# Lab_8_v3.net
KiCad netlist of a schematic drawn in Altium Designer
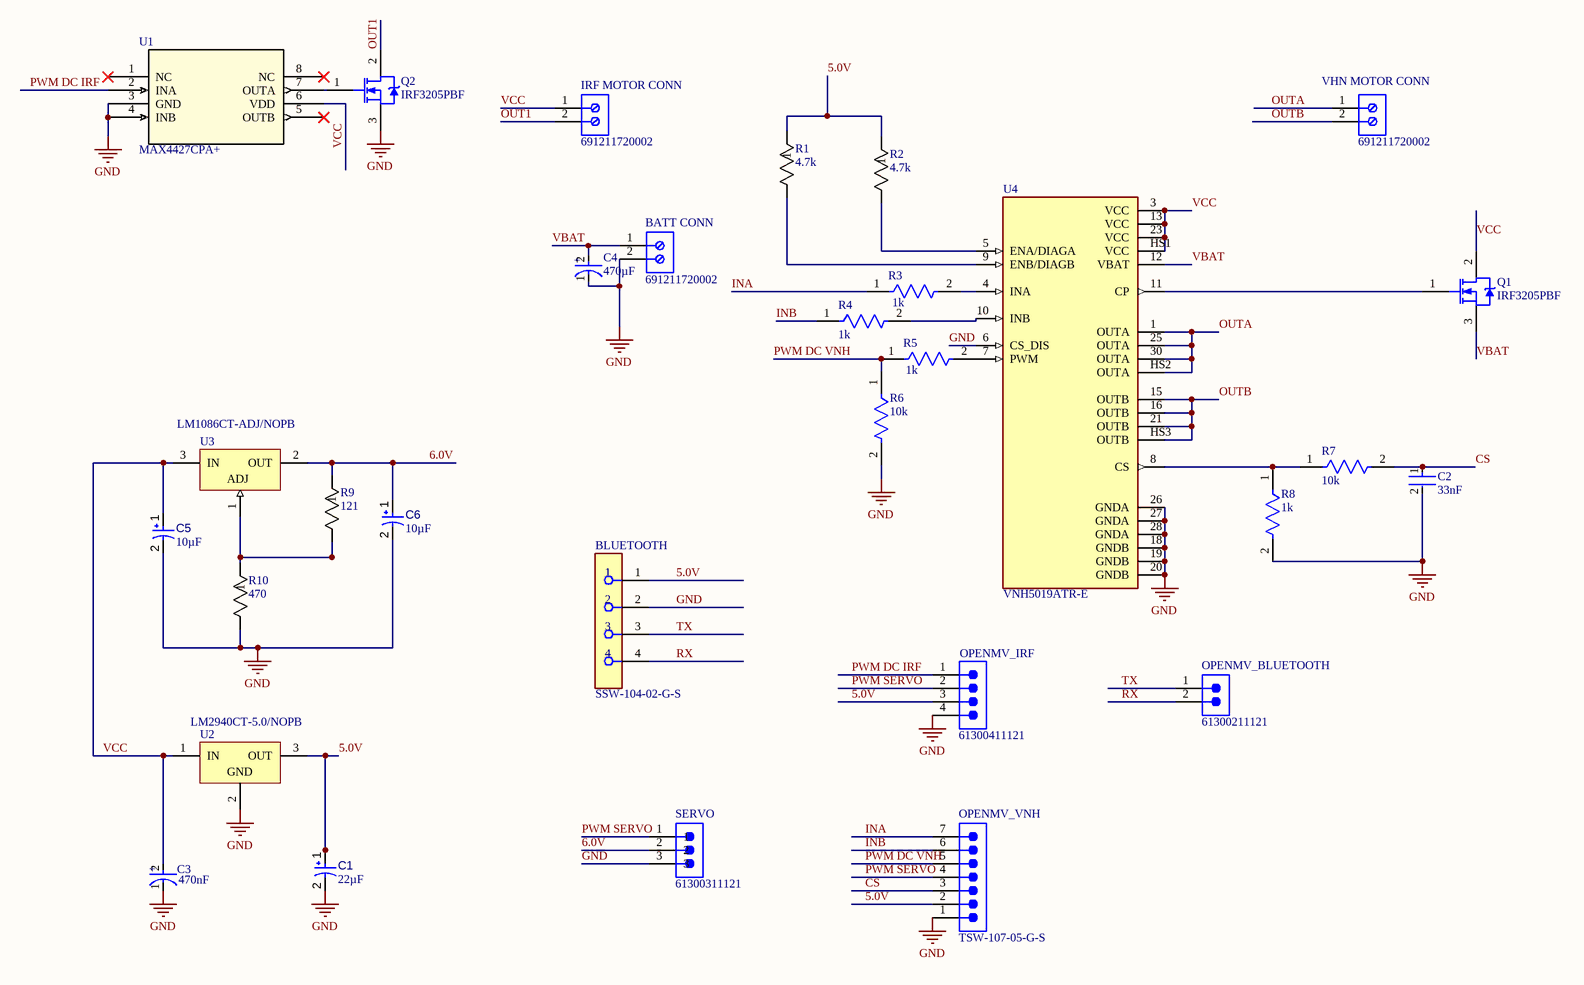
[diagram p0: Lab_8_v3.SchDoc]

(export (version "E")
  (design (tool "Eeschema 10.0.6"))
  (components
    (comp (ref "BATT CONN")
      (value "691211720002")
      (footprint "691211720002")
      (fields (field (name "VOLTAGE") "300V"))
      (libsource (lib "Altium Content Vault") (part "TBL - 1R - 02P - Screw"))
    )
    (comp (ref "BLUETOOTH")
      (value "SSW-104-02-G-S")
      (footprint "FP-SSW-104-02-G-S-MFG")
      (libsource (lib "Haaris Tahir-Kheli") (part "56792406a6bd5c25e158f553ecd1aa7"))
    )
    (comp (ref "C1")
      (value "22µF")
      (footprint "CAPPR55-200-1100X500X1200")
      (description "Aluminum Electrolytic Capacitor, 22 uF, +/- 20%, 50 V, -40 to 85 degC, 2-Pin THD, RoHS, Bulk")
      (fields (field (name "MANUFACTURER") "Panasonic") (field (name "TOLERANCE") "20%"))
      (libsource (lib "University of California, Davis") (part "CAP-P-2"))
    )
    (comp (ref "C2")
      (value "33nF")
      (footprint "FP-565R30GASS33-MFG")
      (description "565R30GASS33 33nF 3 kV dc Ceramic Single Layer Capacitor; Z5U Dielectric Radial 565R Series")
      (fields (field (name "VOLTAGE") "3kV") (field (name "TOLERANCE") "20%"))
      (libsource (lib "Altium Content Vault") (part "02cd4be3c70576c341d710602a673aa"))
    )
    (comp (ref "C3")
      (value "470nF")
      (footprint "FP-RAD-TH-D_5_0_5-L_11_1-MFG")
      (fields (field (name "Comment") "EEU-EB1JR47S"))
      (libsource (lib "Haaris Tahir-Kheli") (part "a00bbbee19879c290e62620ae7e47b1"))
    )
    (comp (ref "C4")
      (value "470µF")
      (footprint "FP-MAL202136471E3-MFG")
      (fields (field (name "Comment") "MAL202136471E3"))
      (libsource (lib "Haaris Tahir-Kheli") (part "a00bbbee19879c290e62620ae7e47b1"))
    )
    (comp (ref "C5")
      (value "10µF")
      (footprint "CAPPR55-200-1100X500X1200")
      (description "Aluminum Electrolytic Capacitor, 10 uF, +/- 20%, 50 V, -40 to 85 degC, 2-Pin THD, RoHS, Bulk")
      (fields (field (name "MANUFACTURER") "Panasonic") (field (name "TOLERANCE") "20%"))
      (libsource (lib "University of California, Davis") (part "CAP-P-2"))
    )
    (comp (ref "C6")
      (value "10µF")
      (footprint "CAPPR55-200-1100X500X1200")
      (description "Aluminum Electrolytic Capacitor, 10 uF, +/- 20%, 50 V, -40 to 85 degC, 2-Pin THD, RoHS, Bulk")
      (fields (field (name "MANUFACTURER") "Panasonic") (field (name "TOLERANCE") "20%"))
      (libsource (lib "University of California, Davis") (part "CAP-P-2"))
    )
    (comp (ref "IRF MOTOR CONN")
      (value "691211720002")
      (footprint "691211720002")
      (fields (field (name "VOLTAGE") "300V"))
      (libsource (lib "Altium Content Vault") (part "TBL - 1R - 02P - Screw"))
    )
    (comp (ref "OPENMV_BLUETOOTH")
      (value "61300211121")
      (footprint "61300211121")
      (libsource (lib "Haaris Tahir-Kheli") (part "Header_Male_1R_02P"))
    )
    (comp (ref "OPENMV_IRF")
      (value "61300411121")
      (footprint "61300411121")
      (libsource (lib "Haaris Tahir-Kheli") (part "Header_Male_1R_04P"))
    )
    (comp (ref "OPENMV_VNH")
      (value "TSW-107-05-G-S")
      (footprint "SMTC-TSW-107-05-X-S")
      (libsource (lib "Haaris Tahir-Kheli") (part "SMTC-TSW-107-05-X-S"))
    )
    (comp (ref "Q1")
      (value "IRF3205PBF")
      (footprint "INF-PG-TO-220AB")
      (libsource (lib "Haaris Tahir-Kheli") (part "NEMOS-GDS-3_B"))
    )
    (comp (ref "Q2")
      (value "IRF3205PBF")
      (footprint "INF-PG-TO-220AB")
      (libsource (lib "Haaris Tahir-Kheli") (part "NEMOS-GDS-3_B"))
    )
    (comp (ref "R1")
      (value "4.7k")
      (footprint "ERL05_VIS")
      (description "Fixed Resistor, Metal Film, 0.125W, 4700ohm, 200V, 2% +/-Tol, 100ppm/Cel, Through Hole Mount")
      (fields (field (name "TOLERANCE") "2%") (field (name "POWER") "125mW"))
      (libsource (lib "Haaris Tahir-Kheli") (part "RLR05C4701GRB14"))
    )
    (comp (ref "R2")
      (value "4.7k")
      (footprint "ERL05_VIS")
      (description "Fixed Resistor, Metal Film, 0.125W, 4700ohm, 200V, 2% +/-Tol, 100ppm/Cel, Through Hole Mount")
      (fields (field (name "TOLERANCE") "2%") (field (name "POWER") "125mW"))
      (libsource (lib "Haaris Tahir-Kheli") (part "RLR05C4701GRB14"))
    )
    (comp (ref "R3")
      (value "1k")
      (footprint "FP-RLR07-MFG")
      (fields (field (name "TOLERANCE") "1%"))
      (libsource (lib "Altium Content Vault") (part "1029c3af85768c4190bb7ad29bc67b5"))
    )
    (comp (ref "R4")
      (value "1k")
      (footprint "FP-RLR07-MFG")
      (fields (field (name "TOLERANCE") "1%"))
      (libsource (lib "Altium Content Vault") (part "1029c3af85768c4190bb7ad29bc67b5"))
    )
    (comp (ref "R5")
      (value "1k")
      (footprint "FP-RLR07-MFG")
      (fields (field (name "TOLERANCE") "1%"))
      (libsource (lib "Altium Content Vault") (part "1029c3af85768c4190bb7ad29bc67b5"))
    )
    (comp (ref "R6")
      (value "10k")
      (footprint "FP-CF18-MFG")
      (description "Fixed Resistor, Carbon Film, 0.125W, 10000ohm, 250V, 5% +/-Tol, -500,0ppm/Cel, Through Hole Mount")
      (fields (field (name "POWER") "125mW") (field (name "TOLERANCE") "5%"))
      (libsource (lib "Haaris Tahir-Kheli") (part "1029c3af85768c4190bb7ad29bc67b5"))
    )
    (comp (ref "R7")
      (value "10k")
      (footprint "FP-CF18-MFG")
      (description "Fixed Resistor, Carbon Film, 0.125W, 10000ohm, 250V, 5% +/-Tol, -500,0ppm/Cel, Through Hole Mount")
      (fields (field (name "POWER") "125mW") (field (name "TOLERANCE") "5%"))
      (libsource (lib "Haaris Tahir-Kheli") (part "1029c3af85768c4190bb7ad29bc67b5"))
    )
    (comp (ref "R8")
      (value "1k")
      (footprint "FP-RLR07-MFG")
      (fields (field (name "TOLERANCE") "1%"))
      (libsource (lib "Altium Content Vault") (part "1029c3af85768c4190bb7ad29bc67b5"))
    )
    (comp (ref "R9")
      (value "121")
      (footprint "SFR16S_VIS")
      (description "Fixed Resistor, Metal Film, 0.5W, 121ohm, 200V, 1% +/-Tol, 100ppm/Cel, Through Hole Mount")
      (fields (field (name "TOLERANCE") "1%") (field (name "POWER") "500mW"))
      (libsource (lib "Haaris Tahir-Kheli") (part "SFR16S0001210FR500"))
    )
    (comp (ref "R10")
      (value "470")
      (footprint "RES_AC03_VIS")
      (description "Fixed Resistor, Wire Wound, 3W, 470ohm, 37.55V, 5% +/-Tol, 100,180ppm/Cel, Through Hole Mount")
      (fields (field (name "TOLERANCE") "5%") (field (name "POWER") "3W"))
      (libsource (lib "Haaris Tahir-Kheli") (part "AC03000004700JAC00"))
    )
    (comp (ref "SERVO")
      (value "61300311121")
      (footprint "61300311121")
      (libsource (lib "Haaris Tahir-Kheli") (part "Header_Male_1R_03P"))
    )
    (comp (ref "U1")
      (value "MAX4427CPA+")
      (footprint "21-0043_P8+2_MXM")
      (description "No Description Available")
      (libsource (lib "Haaris Tahir-Kheli") (part "MAX4427CPA+"))
    )
    (comp (ref "U2")
      (value "LM2940CT-5.0/NOPB")
      (footprint "NDE0003A")
      (description "Fixed Positive LDO Regulator, 5V, 1V Dropout, BIPolar, PSFM3")
      (libsource (lib "Haaris Tahir-Kheli") (part "PM-REG-LM2940-SIL3"))
    )
    (comp (ref "U3")
      (value "LM1086CT-ADJ/NOPB")
      (footprint "NDE0003A")
      (description "Adjustable Positive LDO Regulator, 1.2V Min, 15V Max, 1.5V Dropout, BIPolar, PSFM3")
      (libsource (lib "Haaris Tahir-Kheli") (part "PM-REG-LM1086ADJ-SIL3"))
    )
    (comp (ref "U4")
      (value "VNH5019ATR-E")
      (footprint "IC_VNH5019ATR-E")
      (description "Motor Driver Power MOSFET Parallel, PWM MultiPowerSO-30")
      (fields (field (name "MF") "STMicroelectronics"))
      (libsource (lib "University of California, Davis") (part "VNH5019ATR-E"))
    )
    (comp (ref "VHN MOTOR CONN")
      (value "691211720002")
      (footprint "691211720002")
      (description "Barrier Strip Terminal Block")
      (libsource (lib "Haaris Tahir-Kheli") (part "TBL - 1R - 02P - Screw"))
    )
  )
  (nets
    (net (code "1") (name "/5.0V") (class "Default")
      (node (ref "BLUETOOTH") (pin "1") (pinfunction "1_1") (pintype "passive"))
      (node (ref "C1") (pin "1") (pinfunction "1_1") (pintype "passive"))
      (node (ref "OPENMV_IRF") (pin "3") (pinfunction "3_3") (pintype "passive"))
      (node (ref "OPENMV_VNH") (pin "2") (pinfunction "2_2") (pintype "passive"))
      (node (ref "R1") (pin "1") (pinfunction "1_1") (pintype "passive"))
      (node (ref "R2") (pin "1") (pinfunction "1_1") (pintype "passive"))
      (node (ref "U2") (pin "3") (pinfunction "OUT_3") (pintype "power_in"))
    )
    (net (code "2") (name "/6.0V") (class "Default")
      (node (ref "C6") (pin "1") (pinfunction "1_1") (pintype "passive"))
      (node (ref "R9") (pin "1") (pinfunction "1_1") (pintype "passive"))
      (node (ref "SERVO") (pin "2") (pinfunction "2_2") (pintype "passive"))
      (node (ref "U3") (pin "2") (pinfunction "OUT_2") (pintype "power_in"))
    )
    (net (code "3") (name "/CS") (class "Default")
      (node (ref "C2") (pin "1") (pinfunction "1_1") (pintype "passive"))
      (node (ref "OPENMV_VNH") (pin "3") (pinfunction "3_3") (pintype "passive"))
      (node (ref "R7") (pin "2") (pinfunction "2_2") (pintype "passive"))
    )
    (net (code "4") (name "/INA") (class "Default")
      (node (ref "OPENMV_VNH") (pin "7") (pinfunction "7_7") (pintype "passive"))
      (node (ref "R3") (pin "1") (pinfunction "1_1") (pintype "passive"))
    )
    (net (code "5") (name "/INB") (class "Default")
      (node (ref "OPENMV_VNH") (pin "6") (pinfunction "6_6") (pintype "passive"))
      (node (ref "R4") (pin "1") (pinfunction "1_1") (pintype "passive"))
    )
    (net (code "6") (name "/OUT1") (class "Default")
      (node (ref "IRF MOTOR CONN") (pin "2") (pinfunction "2_2") (pintype "passive"))
      (node (ref "Q2") (pin "2") (pinfunction "D_2") (pintype "passive"))
    )
    (net (code "7") (name "/OUTA") (class "Default")
      (node (ref "U4") (pin "1") (pinfunction "OUTA_1") (pintype "passive"))
      (node (ref "U4") (pin "25") (pinfunction "OUTA_25") (pintype "passive"))
      (node (ref "U4") (pin "30") (pinfunction "OUTA_30") (pintype "passive"))
      (node (ref "U4") (pin "HS2") (pinfunction "OUTA_HS2") (pintype "passive"))
      (node (ref "VHN MOTOR CONN") (pin "1") (pinfunction "1_1") (pintype "passive"))
    )
    (net (code "8") (name "/OUTB") (class "Default")
      (node (ref "U4") (pin "15") (pinfunction "OUTB_15") (pintype "passive"))
      (node (ref "U4") (pin "16") (pinfunction "OUTB_16") (pintype "passive"))
      (node (ref "U4") (pin "21") (pinfunction "OUTB_21") (pintype "passive"))
      (node (ref "U4") (pin "HS3") (pinfunction "OUTB_HS3") (pintype "passive"))
      (node (ref "VHN MOTOR CONN") (pin "2") (pinfunction "2_2") (pintype "passive"))
    )
    (net (code "9") (name "/PWM DC IRF") (class "Default")
      (node (ref "OPENMV_IRF") (pin "1") (pinfunction "1_1") (pintype "passive"))
      (node (ref "U1") (pin "2") (pinfunction "INA_2") (pintype "input"))
    )
    (net (code "10") (name "/PWM DC VNH") (class "Default")
      (node (ref "OPENMV_VNH") (pin "5") (pinfunction "5_5") (pintype "passive"))
      (node (ref "R5") (pin "1") (pinfunction "1_1") (pintype "passive"))
      (node (ref "R6") (pin "1") (pinfunction "1_1") (pintype "passive"))
    )
    (net (code "11") (name "/PWM SERVO") (class "Default")
      (node (ref "OPENMV_IRF") (pin "2") (pinfunction "2_2") (pintype "passive"))
      (node (ref "OPENMV_VNH") (pin "4") (pinfunction "4_4") (pintype "passive"))
      (node (ref "SERVO") (pin "1") (pinfunction "1_1") (pintype "passive"))
    )
    (net (code "12") (name "/RX") (class "Default")
      (node (ref "BLUETOOTH") (pin "4") (pinfunction "4_4") (pintype "passive"))
      (node (ref "OPENMV_BLUETOOTH") (pin "2") (pinfunction "2_2") (pintype "passive"))
    )
    (net (code "13") (name "/TX") (class "Default")
      (node (ref "BLUETOOTH") (pin "3") (pinfunction "3_3") (pintype "passive"))
      (node (ref "OPENMV_BLUETOOTH") (pin "1") (pinfunction "1_1") (pintype "passive"))
    )
    (net (code "14") (name "/VBAT") (class "Default")
      (node (ref "BATT CONN") (pin "1") (pinfunction "1_1") (pintype "passive"))
      (node (ref "C4") (pin "2") (pinfunction "A_2") (pintype "passive"))
      (node (ref "Q1") (pin "3") (pinfunction "S_3") (pintype "passive"))
      (node (ref "U4") (pin "12") (pinfunction "VBAT_12") (pintype "power_in"))
    )
    (net (code "15") (name "/VCC") (class "Default")
      (node (ref "C3") (pin "2") (pinfunction "A_2") (pintype "passive"))
      (node (ref "C5") (pin "1") (pinfunction "1_1") (pintype "passive"))
      (node (ref "IRF MOTOR CONN") (pin "1") (pinfunction "1_1") (pintype "passive"))
      (node (ref "Q1") (pin "2") (pinfunction "D_2") (pintype "passive"))
      (node (ref "U1") (pin "6") (pinfunction "VDD_6") (pintype "power_in"))
      (node (ref "U2") (pin "1") (pinfunction "IN_1") (pintype "power_in"))
      (node (ref "U3") (pin "3") (pinfunction "IN_3") (pintype "power_in"))
      (node (ref "U4") (pin "13") (pinfunction "VCC_13") (pintype "power_in"))
      (node (ref "U4") (pin "23") (pinfunction "VCC_23") (pintype "power_in"))
      (node (ref "U4") (pin "3") (pinfunction "VCC_3") (pintype "power_in"))
      (node (ref "U4") (pin "HS1") (pinfunction "VCC_HS1") (pintype "power_in"))
    )
    (net (code "16") (name "GND") (class "Default")
      (node (ref "BATT CONN") (pin "2") (pinfunction "2_2") (pintype "passive"))
      (node (ref "BLUETOOTH") (pin "2") (pinfunction "2_2") (pintype "passive"))
      (node (ref "C1") (pin "2") (pinfunction "2_2") (pintype "passive"))
      (node (ref "C2") (pin "2") (pinfunction "2_2") (pintype "passive"))
      (node (ref "C3") (pin "1") (pinfunction "C_1") (pintype "passive"))
      (node (ref "C4") (pin "1") (pinfunction "C_1") (pintype "passive"))
      (node (ref "C5") (pin "2") (pinfunction "2_2") (pintype "passive"))
      (node (ref "C6") (pin "2") (pinfunction "2_2") (pintype "passive"))
      (node (ref "OPENMV_IRF") (pin "4") (pinfunction "4_4") (pintype "passive"))
      (node (ref "OPENMV_VNH") (pin "1") (pinfunction "1_1") (pintype "passive"))
      (node (ref "Q2") (pin "3") (pinfunction "S_3") (pintype "passive"))
      (node (ref "R10") (pin "2") (pinfunction "2_2") (pintype "passive"))
      (node (ref "R6") (pin "2") (pinfunction "2_2") (pintype "passive"))
      (node (ref "R8") (pin "2") (pinfunction "2_2") (pintype "passive"))
      (node (ref "SERVO") (pin "3") (pinfunction "3_3") (pintype "passive"))
      (node (ref "U1") (pin "3") (pinfunction "GND_3") (pintype "power_in"))
      (node (ref "U1") (pin "4") (pinfunction "INB_4") (pintype "input"))
      (node (ref "U2") (pin "2") (pinfunction "GND_2") (pintype "power_in"))
      (node (ref "U4") (pin "18") (pinfunction "GNDB_18") (pintype "power_in"))
      (node (ref "U4") (pin "19") (pinfunction "GNDB_19") (pintype "power_in"))
      (node (ref "U4") (pin "20") (pinfunction "GNDB_20") (pintype "power_in"))
      (node (ref "U4") (pin "26") (pinfunction "GNDA_26") (pintype "power_in"))
      (node (ref "U4") (pin "27") (pinfunction "GNDA_27") (pintype "power_in"))
      (node (ref "U4") (pin "28") (pinfunction "GNDA_28") (pintype "power_in"))
      (node (ref "U4") (pin "6") (pinfunction "CS_DIS_6") (pintype "input"))
    )
    (net (code "17") (name "Net-(Q1-G)") (class "Default")
      (node (ref "Q1") (pin "1") (pinfunction "G_1") (pintype "passive"))
      (node (ref "U4") (pin "11") (pinfunction "CP_11") (pintype "output"))
    )
    (net (code "18") (name "Net-(Q2-G)") (class "Default")
      (node (ref "Q2") (pin "1") (pinfunction "G_1") (pintype "passive"))
      (node (ref "U1") (pin "7") (pinfunction "OUTA_7") (pintype "output"))
    )
    (net (code "19") (name "Net-(U3-ADJ)") (class "Default")
      (node (ref "R10") (pin "1") (pinfunction "1_1") (pintype "passive"))
      (node (ref "R9") (pin "2") (pinfunction "2_2") (pintype "passive"))
      (node (ref "U3") (pin "1") (pinfunction "ADJ_1") (pintype "input"))
    )
    (net (code "20") (name "Net-(U4-CS)") (class "Default")
      (node (ref "R7") (pin "1") (pinfunction "1_1") (pintype "passive"))
      (node (ref "R8") (pin "1") (pinfunction "1_1") (pintype "passive"))
      (node (ref "U4") (pin "8") (pinfunction "CS_8") (pintype "output"))
    )
    (net (code "21") (name "Net-(U4-ENA{slash}DIAGA)") (class "Default")
      (node (ref "R2") (pin "2") (pinfunction "2_2") (pintype "passive"))
      (node (ref "U4") (pin "5") (pinfunction "ENA/DIAGA_5") (pintype "input"))
    )
    (net (code "22") (name "Net-(U4-ENB{slash}DIAGB)") (class "Default")
      (node (ref "R1") (pin "2") (pinfunction "2_2") (pintype "passive"))
      (node (ref "U4") (pin "9") (pinfunction "ENB/DIAGB_9") (pintype "input"))
    )
    (net (code "23") (name "Net-(U4-INA)") (class "Default")
      (node (ref "R3") (pin "2") (pinfunction "2_2") (pintype "passive"))
      (node (ref "U4") (pin "4") (pinfunction "INA_4") (pintype "input"))
    )
    (net (code "24") (name "Net-(U4-INB)") (class "Default")
      (node (ref "R4") (pin "2") (pinfunction "2_2") (pintype "passive"))
      (node (ref "U4") (pin "10") (pinfunction "INB_10") (pintype "input"))
    )
    (net (code "25") (name "Net-(U4-PWM)") (class "Default")
      (node (ref "R5") (pin "2") (pinfunction "2_2") (pintype "passive"))
      (node (ref "U4") (pin "7") (pinfunction "PWM_7") (pintype "input"))
    )
    (net (code "26") (name "unconnected-(U1-NC-Pad1)") (class "Default")
      (node (ref "U1") (pin "1") (pinfunction "NC_1") (pintype "passive+no_connect"))
    )
    (net (code "27") (name "unconnected-(U1-NC-Pad8)") (class "Default")
      (node (ref "U1") (pin "8") (pinfunction "NC_8") (pintype "passive+no_connect"))
    )
    (net (code "28") (name "unconnected-(U1-OUTB-Pad5)") (class "Default")
      (node (ref "U1") (pin "5") (pinfunction "OUTB_5") (pintype "output+no_connect"))
    )
  )
)
